# Senior_DoorLock.net
KiCad netlist of a schematic drawn in Altium Designer
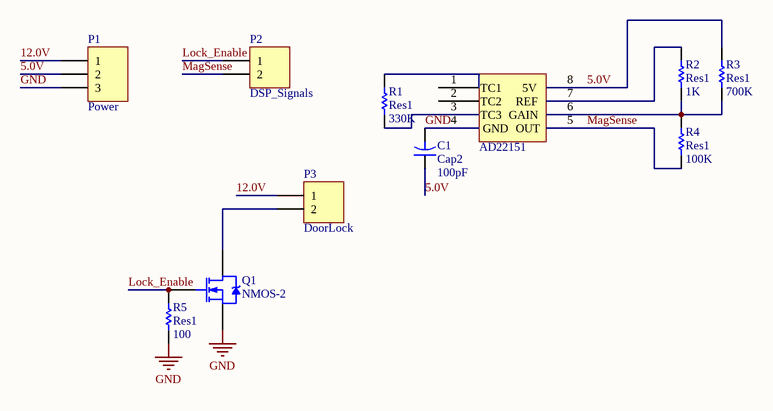
[diagram p0: Senior_DoorLock.SchDoc]

(export (version "E")
  (design (tool "Eeschema 10.0.6"))
  (components
    (comp (ref "AD22151")
      (value "AD22151 Breakout")
      (footprint "Miscellaneous Devices:DIP-8")
      (description "Magnetic Field Sensor")
      (libsource (lib "AD22151") (part "AD22151 Breakout"))
    )
    (comp (ref "C1")
      (value "Cap2")
      (footprint "CAPR5-4X5")
      (description "Capacitor")
      (fields (field (name "ALTIUM_VALUE") "100pF") (field (name "PUBLISHER") "Altium Limited"))
      (libsource (lib "Miscellaneous Devices") (part "Cap2"))
    )
    (comp (ref "P1")
      (value "Power")
      (footprint "HDR1X3")
      (description "Header, 3-Pin")
      (fields (field (name "PUBLISHER") "Altium Limited"))
      (libsource (lib "Miscellaneous Connectors") (part "Header 3"))
    )
    (comp (ref "P2")
      (value "DSP_Signals")
      (footprint "HDR1X2")
      (description "Header, 2-Pin")
      (fields (field (name "PUBLISHER") "Altium Limited"))
      (libsource (lib "Miscellaneous Connectors") (part "Header 2"))
    )
    (comp (ref "P3")
      (value "DoorLock")
      (footprint "HDR1X2")
      (description "Header, 2-Pin")
      (fields (field (name "PUBLISHER") "Altium Limited"))
      (libsource (lib "Miscellaneous Connectors") (part "Header 2"))
    )
    (comp (ref "Q1")
      (value "NMOS-2")
      (footprint "TO-220AB")
      (description "N-Channel Power MOSFET")
      (fields (field (name "PUBLISHER") "Altium Limited"))
      (libsource (lib "Miscellaneous Devices") (part "NMOS-2"))
    )
    (comp (ref "R1")
      (value "Res1")
      (footprint "AXIAL-0.3")
      (description "Resistor")
      (fields (field (name "ALTIUM_VALUE") "330K") (field (name "PUBLISHER") "Altium Limited"))
      (libsource (lib "Miscellaneous Devices") (part "Res1"))
    )
    (comp (ref "R2")
      (value "Res1")
      (footprint "AXIAL-0.3")
      (description "Resistor")
      (fields (field (name "ALTIUM_VALUE") "1K") (field (name "PUBLISHER") "Altium Limited"))
      (libsource (lib "Miscellaneous Devices") (part "Res1"))
    )
    (comp (ref "R3")
      (value "Res1")
      (footprint "AXIAL-0.3")
      (description "Resistor")
      (fields (field (name "ALTIUM_VALUE") "700K") (field (name "PUBLISHER") "Altium Limited"))
      (libsource (lib "Miscellaneous Devices") (part "Res1"))
    )
    (comp (ref "R4")
      (value "Res1")
      (footprint "AXIAL-0.3")
      (description "Resistor")
      (fields (field (name "ALTIUM_VALUE") "100K") (field (name "PUBLISHER") "Altium Limited"))
      (libsource (lib "Miscellaneous Devices") (part "Res1"))
    )
    (comp (ref "R5")
      (value "Res1")
      (footprint "AXIAL-0.3")
      (description "Resistor")
      (fields (field (name "ALTIUM_VALUE") "100") (field (name "PUBLISHER") "Altium Limited"))
      (libsource (lib "Miscellaneous Devices") (part "Res1"))
    )
  )
  (nets
    (net (code "1") (name "/5.0V") (class "Default")
      (node (ref "AD22151") (pin "8") (pinfunction "5V_8") (pintype "passive"))
      (node (ref "C1") (pin "1") (pinfunction "1_1") (pintype "passive"))
      (node (ref "P1") (pin "2") (pinfunction "2_2") (pintype "passive"))
      (node (ref "R3") (pin "2") (pinfunction "2_2") (pintype "passive"))
    )
    (net (code "2") (name "/12.0V") (class "Default")
      (node (ref "P1") (pin "1") (pinfunction "1_1") (pintype "passive"))
      (node (ref "P3") (pin "1") (pinfunction "1_1") (pintype "passive"))
    )
    (net (code "3") (name "/Lock_Enable") (class "Default")
      (node (ref "P2") (pin "1") (pinfunction "1_1") (pintype "passive"))
      (node (ref "Q1") (pin "1") (pinfunction "G_1") (pintype "passive"))
      (node (ref "R5") (pin "2") (pinfunction "2_2") (pintype "passive"))
    )
    (net (code "4") (name "/MagSense") (class "Default")
      (node (ref "AD22151") (pin "5") (pinfunction "OUT_5") (pintype "passive"))
      (node (ref "P2") (pin "2") (pinfunction "2_2") (pintype "passive"))
      (node (ref "R4") (pin "1") (pinfunction "1_1") (pintype "passive"))
    )
    (net (code "5") (name "GND") (class "Default")
      (node (ref "AD22151") (pin "4") (pinfunction "GND_4") (pintype "passive"))
      (node (ref "C1") (pin "2") (pinfunction "2_2") (pintype "passive"))
      (node (ref "P1") (pin "3") (pinfunction "3_3") (pintype "passive"))
      (node (ref "Q1") (pin "3") (pinfunction "S_3") (pintype "passive"))
      (node (ref "R5") (pin "1") (pinfunction "1_1") (pintype "passive"))
    )
    (net (code "6") (name "Net-(AD22151-GAIN)") (class "Default")
      (node (ref "AD22151") (pin "6") (pinfunction "GAIN_6") (pintype "passive"))
      (node (ref "R2") (pin "1") (pinfunction "1_1") (pintype "passive"))
      (node (ref "R3") (pin "1") (pinfunction "1_1") (pintype "passive"))
      (node (ref "R4") (pin "2") (pinfunction "2_2") (pintype "passive"))
    )
    (net (code "7") (name "Net-(AD22151-REF)") (class "Default")
      (node (ref "AD22151") (pin "7") (pinfunction "REF_7") (pintype "passive"))
      (node (ref "R2") (pin "2") (pinfunction "2_2") (pintype "passive"))
    )
    (net (code "8") (name "Net-(AD22151-TC1)") (class "Default")
      (node (ref "AD22151") (pin "1") (pinfunction "TC1_1") (pintype "passive"))
      (node (ref "R1") (pin "2") (pinfunction "2_2") (pintype "passive"))
    )
    (net (code "9") (name "Net-(AD22151-TC3)") (class "Default")
      (node (ref "AD22151") (pin "3") (pinfunction "TC3_3") (pintype "passive"))
      (node (ref "R1") (pin "1") (pinfunction "1_1") (pintype "passive"))
    )
    (net (code "10") (name "Net-(Q1-D)") (class "Default")
      (node (ref "P3") (pin "2") (pinfunction "2_2") (pintype "passive"))
      (node (ref "Q1") (pin "2") (pinfunction "D_2") (pintype "passive"))
    )
    (net (code "11") (name "unconnected-(AD22151-TC2-Pad2)") (class "Default")
      (node (ref "AD22151") (pin "2") (pinfunction "TC2_2") (pintype "passive"))
    )
  )
)
